# ha_light_switch-power.net
KiCad netlist of a schematic drawn in Altium Designer
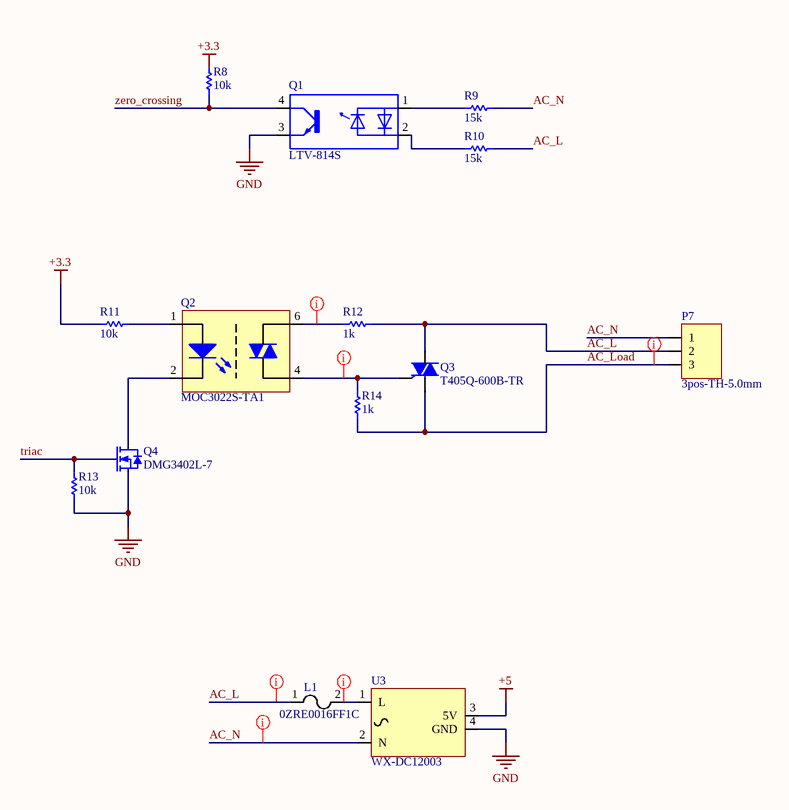
[diagram p0: ha_light_switch-power.SchDoc]

(export (version "E")
  (design (tool "Eeschema 10.0.6"))
  (components
    (comp (ref "L1")
      (value "0ZRE0016FF1C")
      (footprint "0ZRE0016FF1C-PTC")
      (description "PTC RESET FUSE 240V 160MA RADIAL")
      (libsource (lib "Fuses") (part "0ZRE0016FF1C"))
    )
    (comp (ref "P7")
      (value "3pos-TH-5.0mm")
      (footprint "Weco 3")
      (description "3pos-TH-5.0mm Screw Terminal")
      (libsource (lib "ScrewTerminal") (part "3P-TH-5.0mm"))
    )
    (comp (ref "Q1")
      (value "LTV-814S")
      (footprint "SMD-4-LTV814")
      (description "Optoisolator Transistor Output 5000Vrms 1 Channel 4-SMD")
      (libsource (lib "OptoAndDigitalIsolators") (part "LTV-814S"))
    )
    (comp (ref "Q2")
      (value "MOC3022S-TA1")
      (footprint "SMD-6")
      (description "OPTOISOLATOR 5KV TRIAC 6SMD")
      (libsource (lib "OptoAndDigitalIsolators") (part "MOC3022S-TA1"))
    )
    (comp (ref "Q3")
      (value "T405Q-600B-TR")
      (footprint "TO-252-3/DPAK")
      (description "TRIAC SENS GATE 600V 4A DPAK")
      (libsource (lib "Triac") (part "T405Q-600B-TR"))
    )
    (comp (ref "Q4")
      (value "DMG3402L-7")
      (footprint "SOT-23-3")
      (description "N-Channel 30 V 4A (Ta) 1.4W (Ta) Surface Mount SOT-23-3")
      (libsource (lib "FET-N-Small") (part "DMG3402L-7"))
    )
    (comp (ref "R8")
      (value "10k")
      (footprint "Resistor-0603")
      (description "Resistor0603-10k")
      (fields (field (name "Comment") "SMT resistor"))
      (libsource (lib "Resistors") (part "Resistor-0603-10k"))
    )
    (comp (ref "R9")
      (value "15k")
      (footprint "RESISTOR-2512")
      (description "Resistor-2512-15k")
      (fields (field (name "Comment") "SMT resistor"))
      (libsource (lib "Resistors") (part "Resistor-2512-15k"))
    )
    (comp (ref "R10")
      (value "15k")
      (footprint "RESISTOR-2512")
      (description "Resistor-2512-15k")
      (fields (field (name "Comment") "SMT resistor"))
      (libsource (lib "Resistors") (part "Resistor-2512-15k"))
    )
    (comp (ref "R11")
      (value "10k")
      (footprint "Resistor-0603")
      (description "Resistor0603-10k")
      (fields (field (name "Comment") "SMT resistor"))
      (libsource (lib "Resistors") (part "Resistor-0603-10k"))
    )
    (comp (ref "R12")
      (value "1k")
      (footprint "RESISTOR-2512")
      (description "Resistor-2512-1k")
      (fields (field (name "Comment") "SMT resistor"))
      (libsource (lib "Resistors") (part "Resistor-2512-1k"))
    )
    (comp (ref "R13")
      (value "10k")
      (footprint "Resistor-0603")
      (description "Resistor0603-10k")
      (fields (field (name "Comment") "SMT resistor"))
      (libsource (lib "Resistors") (part "Resistor-0603-10k"))
    )
    (comp (ref "R14")
      (value "1k")
      (footprint "RESISTOR-2512")
      (description "Resistor-2512-1k")
      (fields (field (name "Comment") "SMT resistor"))
      (libsource (lib "Resistors") (part "Resistor-2512-1k"))
    )
    (comp (ref "U3")
      (value "WX-DC12003")
      (footprint "WX-DC12003")
      (description "AC/DC Isolated converter. 50-277AC -> 5Vdc")
      (libsource (lib "PMIC-VoltageRegulators-ACDC") (part "WX-DC12003"))
    )
  )
  (nets
    (net (code "1") (name "+3.3") (class "Default")
      (node (ref "R11") (pin "2") (pinfunction "2_2") (pintype "passive"))
      (node (ref "R8") (pin "2") (pinfunction "2_2") (pintype "passive"))
    )
    (net (code "2") (name "+5") (class "Default")
      (node (ref "U3") (pin "3") (pinfunction "5V_3") (pintype "passive"))
    )
    (net (code "3") (name "/AC_L") (class "Default")
      (node (ref "L1") (pin "1") (pinfunction "1_1") (pintype "passive"))
      (node (ref "P7") (pin "2") (pinfunction "2_2") (pintype "passive"))
      (node (ref "Q3") (pin "2") (pinfunction "A2_2") (pintype "passive"))
      (node (ref "R10") (pin "2") (pinfunction "2_2") (pintype "passive"))
      (node (ref "R12") (pin "2") (pinfunction "2_2") (pintype "passive"))
    )
    (net (code "4") (name "/AC_Load") (class "Default")
      (node (ref "P7") (pin "3") (pinfunction "3_3") (pintype "passive"))
      (node (ref "Q3") (pin "1") (pinfunction "A1_1") (pintype "passive"))
      (node (ref "R14") (pin "1") (pinfunction "1_1") (pintype "passive"))
    )
    (net (code "5") (name "/AC_N") (class "Default")
      (node (ref "P7") (pin "1") (pinfunction "1_1") (pintype "passive"))
      (node (ref "R9") (pin "2") (pinfunction "2_2") (pintype "passive"))
      (node (ref "U3") (pin "2") (pinfunction "N_2") (pintype "passive"))
    )
    (net (code "6") (name "/triac") (class "Default")
      (node (ref "Q4") (pin "1") (pinfunction "G_1") (pintype "passive"))
      (node (ref "R13") (pin "1") (pinfunction "1_1") (pintype "passive"))
    )
    (net (code "7") (name "/zero_crossing") (class "Default")
      (node (ref "Q1") (pin "4") (pinfunction "4_4") (pintype "passive"))
      (node (ref "R8") (pin "1") (pinfunction "1_1") (pintype "passive"))
    )
    (net (code "8") (name "GND") (class "Default")
      (node (ref "Q1") (pin "3") (pinfunction "3_3") (pintype "passive"))
      (node (ref "Q4") (pin "2") (pinfunction "S_2") (pintype "passive"))
      (node (ref "R13") (pin "2") (pinfunction "2_2") (pintype "passive"))
      (node (ref "U3") (pin "4") (pinfunction "GND_4") (pintype "passive"))
    )
    (net (code "9") (name "Net-(Q1-Pad1)") (class "Default")
      (node (ref "Q1") (pin "1") (pinfunction "1_1") (pintype "passive"))
      (node (ref "R9") (pin "1") (pinfunction "1_1") (pintype "passive"))
    )
    (net (code "10") (name "Net-(Q1-Pad2)") (class "Default")
      (node (ref "Q1") (pin "2") (pinfunction "2_2") (pintype "passive"))
      (node (ref "R10") (pin "1") (pinfunction "1_1") (pintype "passive"))
    )
    (net (code "11") (name "Net-(Q2-Anode)") (class "Default")
      (node (ref "Q2") (pin "1") (pinfunction "Anode_1") (pintype "passive"))
      (node (ref "R11") (pin "1") (pinfunction "1_1") (pintype "passive"))
    )
    (net (code "12") (name "Net-(Q2-Cathode)") (class "Default")
      (node (ref "Q2") (pin "2") (pinfunction "Cathode_2") (pintype "passive"))
      (node (ref "Q4") (pin "3") (pinfunction "D_3") (pintype "passive"))
    )
    (net (code "13") (name "Net-(Q2-GND)") (class "Default")
      (node (ref "Q2") (pin "4") (pinfunction "GND_4") (pintype "passive"))
      (node (ref "Q3") (pin "3") (pinfunction "G_3") (pintype "passive"))
      (node (ref "R14") (pin "2") (pinfunction "2_2") (pintype "passive"))
    )
    (net (code "14") (name "Net-(Q2-Vdd)") (class "Default")
      (node (ref "Q2") (pin "6") (pinfunction "Vdd_6") (pintype "passive"))
      (node (ref "R12") (pin "1") (pinfunction "1_1") (pintype "passive"))
    )
    (net (code "15") (name "Net-(U3-L)") (class "Default")
      (node (ref "L1") (pin "2") (pinfunction "2_2") (pintype "passive"))
      (node (ref "U3") (pin "1") (pinfunction "L_1") (pintype "passive"))
    )
  )
)
